# 6_audioCodec.net
KiCad netlist of a schematic drawn in Altium Designer
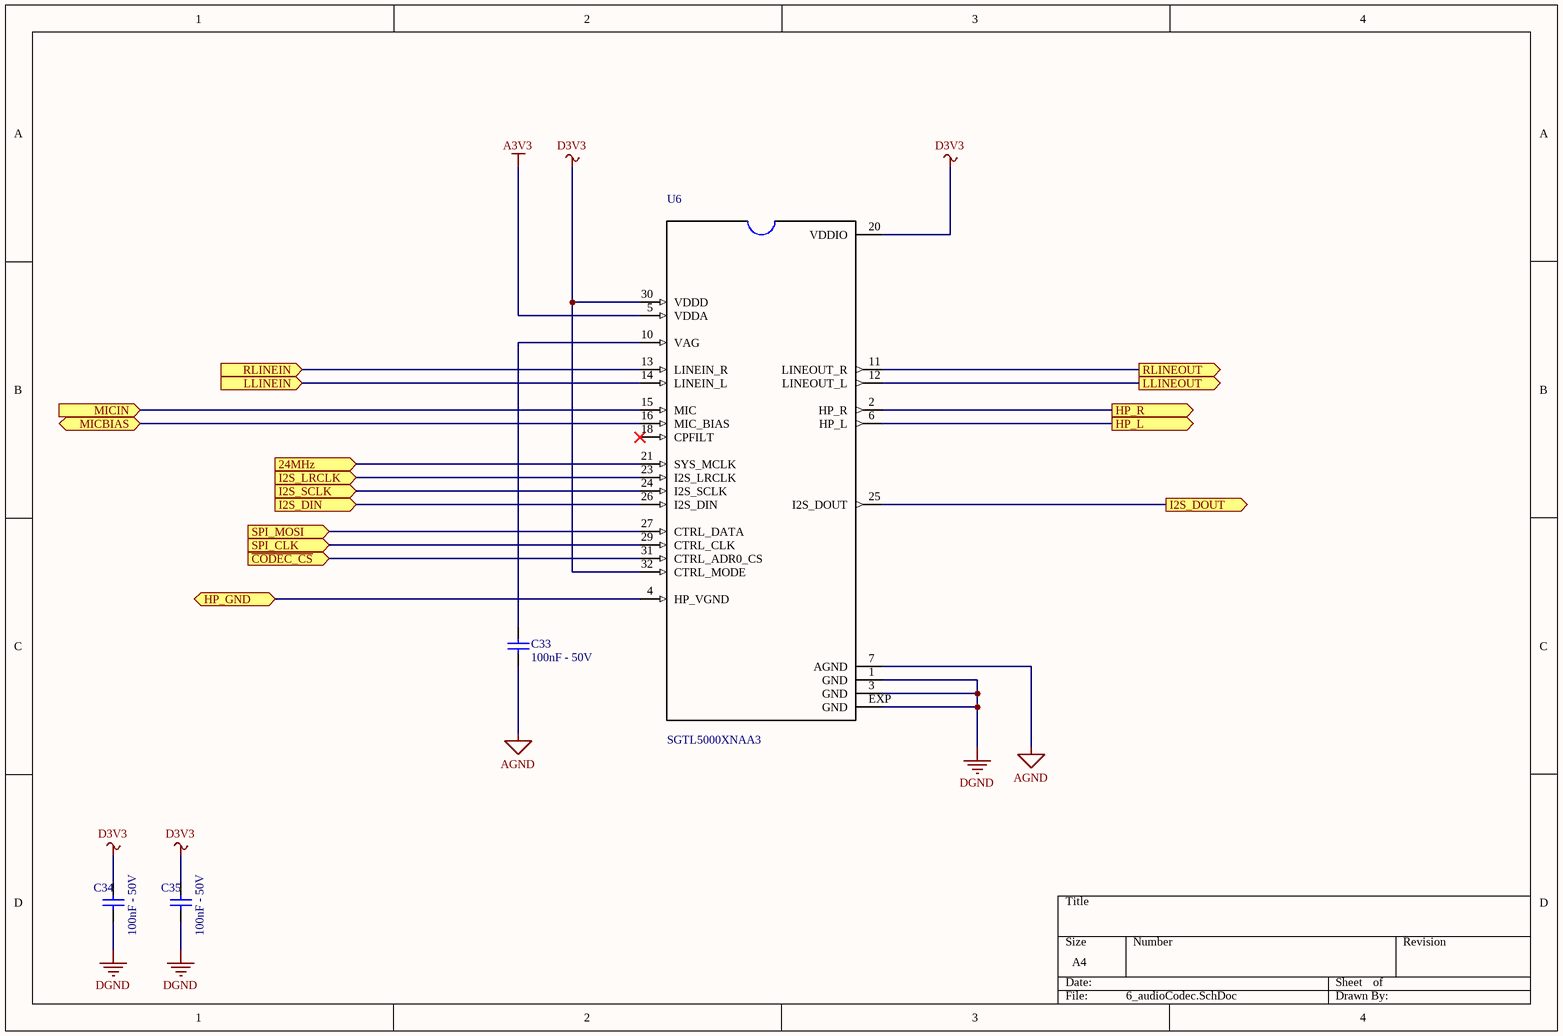
[diagram p0: 6_audioCodec.SchDoc]

(export (version "E")
  (design (tool "Eeschema 10.0.6"))
  (components
    (comp (ref "C33")
      (value "Capacitor 100 nF - 10%")
      (footprint "SMD0805-CAP")
      (description "Capacitor 100nF, 10%, SMD 0805")
      (fields
        (field (name "MANUFACTURER") "AVX")
        (field (name "PARTNUMBER") "08055C104KAT2A")
        (field (name "VALOR") "100nF - 50V")
      )
      (libsource (lib "Capacitor_smd") (part "100nF - 50V - 10% - 0805 - 580"))
    )
    (comp (ref "C34")
      (value "Capacitor 100 nF - 10%")
      (footprint "SMD0805-CAP")
      (description "Capacitor 100nF, 10%, SMD 0805")
      (fields
        (field (name "MANUFACTURER") "AVX")
        (field (name "PARTNUMBER") "08055C104KAT2A")
        (field (name "VALOR") "100nF - 50V")
      )
      (libsource (lib "Capacitor_smd") (part "100nF - 50V - 10% - 0805 - 580"))
    )
    (comp (ref "C35")
      (value "Capacitor 100 nF - 10%")
      (footprint "SMD0805-CAP")
      (description "Capacitor 100nF, 10%, SMD 0805")
      (fields
        (field (name "MANUFACTURER") "AVX")
        (field (name "PARTNUMBER") "08055C104KAT2A")
        (field (name "VALOR") "100nF - 50V")
      )
      (libsource (lib "Capacitor_smd") (part "100nF - 50V - 10% - 0805 - 580"))
    )
    (comp (ref "U6")
      (value "SGTL5000XNAA3")
      (footprint "QFN50P500X500X100-33N_SGTL5000XNAA3(Primary)")
      (description "Audio Codec , Ultra Low-Power, 4 mw for DAC-to-HP, 98 dB SNR and -80 dB THD+N, QFN 32, Tray")
      (fields (field (name "MF") "NXP Semiconductors"))
      (libsource (lib "SGTL5000XNAA3") (part "SGTL5000XNAA3"))
    )
  )
  (nets
    (net (code "1") (name "/24MHz") (class "Default")
      (node (ref "U6") (pin "21") (pinfunction "SYS_MCLK_21") (pintype "input"))
    )
    (net (code "2") (name "/CODEC_CS") (class "Default")
      (node (ref "U6") (pin "31") (pinfunction "CTRL_ADR0_CS_31") (pintype "input"))
    )
    (net (code "3") (name "/HP_GND") (class "Default")
      (node (ref "U6") (pin "4") (pinfunction "HP_VGND_4") (pintype "input"))
    )
    (net (code "4") (name "/HP_L") (class "Default")
      (node (ref "U6") (pin "6") (pinfunction "HP_L_6") (pintype "output"))
    )
    (net (code "5") (name "/HP_R") (class "Default")
      (node (ref "U6") (pin "2") (pinfunction "HP_R_2") (pintype "output"))
    )
    (net (code "6") (name "/I2S_DIN") (class "Default")
      (node (ref "U6") (pin "26") (pinfunction "I2S_DIN_26") (pintype "input"))
    )
    (net (code "7") (name "/I2S_DOUT") (class "Default")
      (node (ref "U6") (pin "25") (pinfunction "I2S_DOUT_25") (pintype "output"))
    )
    (net (code "8") (name "/I2S_LRCLK") (class "Default")
      (node (ref "U6") (pin "23") (pinfunction "I2S_LRCLK_23") (pintype "input"))
    )
    (net (code "9") (name "/I2S_SCLK") (class "Default")
      (node (ref "U6") (pin "24") (pinfunction "I2S_SCLK_24") (pintype "input"))
    )
    (net (code "10") (name "/LLINEIN") (class "Default")
      (node (ref "U6") (pin "14") (pinfunction "LINEIN_L_14") (pintype "input"))
    )
    (net (code "11") (name "/LLINEOUT") (class "Default")
      (node (ref "U6") (pin "12") (pinfunction "LINEOUT_L_12") (pintype "output"))
    )
    (net (code "12") (name "/MICBIAS") (class "Default")
      (node (ref "U6") (pin "16") (pinfunction "MIC_BIAS_16") (pintype "input"))
    )
    (net (code "13") (name "/MICIN") (class "Default")
      (node (ref "U6") (pin "15") (pinfunction "MIC_15") (pintype "input"))
    )
    (net (code "14") (name "/RLINEIN") (class "Default")
      (node (ref "U6") (pin "13") (pinfunction "LINEIN_R_13") (pintype "input"))
    )
    (net (code "15") (name "/RLINEOUT") (class "Default")
      (node (ref "U6") (pin "11") (pinfunction "LINEOUT_R_11") (pintype "output"))
    )
    (net (code "16") (name "/SPI_CLK") (class "Default")
      (node (ref "U6") (pin "29") (pinfunction "CTRL_CLK_29") (pintype "input"))
    )
    (net (code "17") (name "/SPI_MOSI") (class "Default")
      (node (ref "U6") (pin "27") (pinfunction "CTRL_DATA_27") (pintype "input"))
    )
    (net (code "18") (name "A3V3") (class "Default")
      (node (ref "U6") (pin "5") (pinfunction "VDDA_5") (pintype "input"))
    )
    (net (code "19") (name "AGND") (class "Default")
      (node (ref "C33") (pin "1") (pinfunction "1_1") (pintype "passive"))
      (node (ref "U6") (pin "7") (pinfunction "AGND_7") (pintype "passive"))
    )
    (net (code "20") (name "D3V3") (class "Default")
      (node (ref "C34") (pin "1") (pinfunction "1_1") (pintype "passive"))
      (node (ref "C35") (pin "1") (pinfunction "1_1") (pintype "passive"))
      (node (ref "U6") (pin "20") (pinfunction "VDDIO_20") (pintype "power_in"))
      (node (ref "U6") (pin "30") (pinfunction "VDDD_30") (pintype "input"))
      (node (ref "U6") (pin "32") (pinfunction "CTRL_MODE_32") (pintype "input"))
    )
    (net (code "21") (name "DGND") (class "Default")
      (node (ref "C34") (pin "2") (pinfunction "2_2") (pintype "passive"))
      (node (ref "C35") (pin "2") (pinfunction "2_2") (pintype "passive"))
      (node (ref "U6") (pin "1") (pinfunction "GND_1") (pintype "passive"))
      (node (ref "U6") (pin "3") (pinfunction "GND_3") (pintype "passive"))
      (node (ref "U6") (pin "EXP") (pinfunction "GND_EXP") (pintype "passive"))
    )
    (net (code "22") (name "Net-(U6-VAG)") (class "Default")
      (node (ref "C33") (pin "2") (pinfunction "2_2") (pintype "passive"))
      (node (ref "U6") (pin "10") (pinfunction "VAG_10") (pintype "input"))
    )
    (net (code "23") (name "unconnected-(U6-CPFILT-Pad18)") (class "Default")
      (node (ref "U6") (pin "18") (pinfunction "CPFILT_18") (pintype "input+no_connect"))
    )
  )
)
